# FD_Capacitance_Sensor_v13B.net
KiCad netlist of a schematic drawn in EAGLE
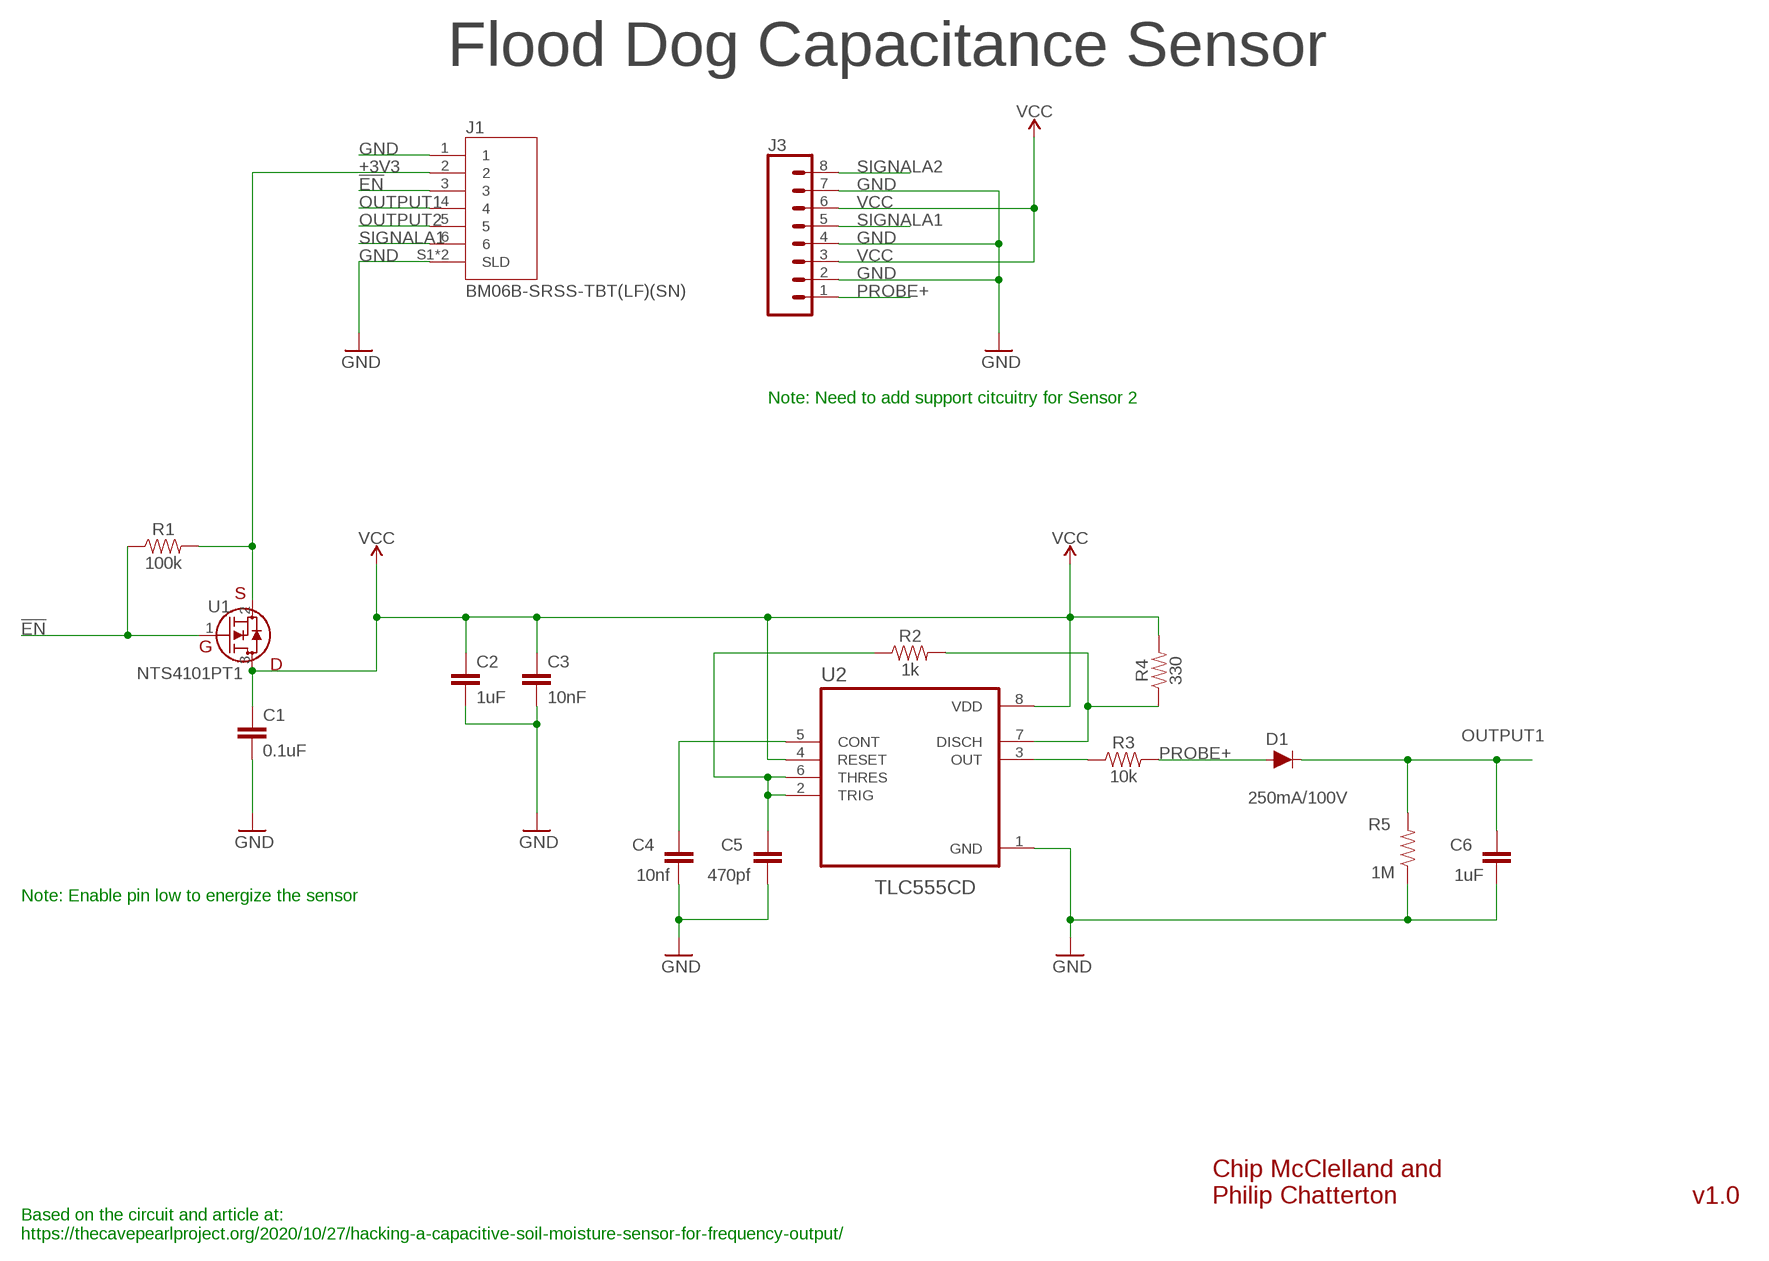
[diagram p0: schematic, sheet 1]

(export (version "E")
  (design (tool "Eeschema 10.0.6"))
  (components
    (comp (ref "C1")
      (value "0.1uF")
      (footprint "eagle-import:0805@1")
      (fields (field (name "HOUSEPART") "YES") (field (name "MPN") "MF-CAP-0805-0.1uF"))
      (libsource (lib "eagle-import") (part "CAP-MF-0.1UF-0805"))
    )
    (comp (ref "C2")
      (value "1uF")
      (footprint "eagle-import:0805@1")
      (fields (field (name "HOUSEPART") "yes") (field (name "MPN") "MF-CAP-0805-1uF"))
      (libsource (lib "eagle-import") (part "CAP-MF-1UF-0805"))
    )
    (comp (ref "C3")
      (value "10nF")
      (footprint "eagle-import:0805@1")
      (fields (field (name "HOUSEPART") "NO") (field (name "MPN") "C0805X103K1RAC3316"))
      (libsource (lib "eagle-import") (part "CAP-10NF-0805"))
    )
    (comp (ref "C4")
      (value "10nf")
      (footprint "eagle-import:C0805")
      (libsource (lib "eagle-import") (part "C-EUC0805"))
    )
    (comp (ref "C5")
      (value "470pf")
      (footprint "eagle-import:C0805")
      (libsource (lib "eagle-import") (part "C-EUC0805"))
    )
    (comp (ref "C6")
      (value "1uF")
      (footprint "eagle-import:C0805")
      (libsource (lib "eagle-import") (part "C-EUC0805"))
    )
    (comp (ref "D1")
      (value "250mA/100V")
      (footprint "eagle-import:SOD-323")
      (fields (field (name "MPN") "BAS16HT1G"))
      (libsource (lib "eagle-import") (part "DIODE-BAS16J"))
    )
    (comp (ref "J1")
      (value "BM06B-SRSS-TBT(LF)(SN)")
      (footprint "eagle-import:JST_BM06B-SRSS-TB(LF)(SN)")
      (libsource (lib "eagle-import") (part "BM06B-SRSS-TBT(LF)(SN)"))
    )
    (comp (ref "J3")
      (value "CONN_08\"")
      (footprint "eagle-import:1X08")
      (libsource (lib "eagle-import") (part "CONN_08{dblquote}"))
    )
    (comp (ref "R1")
      (value "100k")
      (footprint "eagle-import:0805")
      (fields (field (name "MPN") "MF-RES-0805-100K") (field (name "MPN_1") "MF-RES-0805-100K"))
      (libsource (lib "eagle-import") (part "RESISTOR-MF-100K-0805"))
    )
    (comp (ref "R2")
      (value "1k")
      (footprint "eagle-import:0805")
      (fields (field (name "HOUSEPART") "YES") (field (name "MPN") "MF-RES-0805-1K"))
      (libsource (lib "eagle-import") (part "RESISTOR-MF-1K-0805"))
    )
    (comp (ref "R3")
      (value "10k")
      (footprint "eagle-import:0805")
      (fields (field (name "MPN") "MF-RES-0805-10K"))
      (libsource (lib "eagle-import") (part "RESISTOR-MF-10K-0805"))
    )
    (comp (ref "R4")
      (value "330")
      (footprint "eagle-import:0805")
      (fields (field (name "HOUSEPART") "YES") (field (name "MPN") "MF-RES-0805-330"))
      (libsource (lib "eagle-import") (part "RESISTOR-MF-330-0805"))
    )
    (comp (ref "R5")
      (value "1M")
      (footprint "eagle-import:0805")
      (fields (field (name "HOUSEPART") "YES") (field (name "MPN") "MF-RES-0805-1K"))
      (libsource (lib "eagle-import") (part "RESISTOR-MF-1K-0805"))
    )
    (comp (ref "U1")
      (value "NTS4101PT1")
      (footprint "eagle-import:SOT_101PT1_ONS")
      (libsource (lib "eagle-import") (part "NTS4101PT1"))
    )
    (comp (ref "U2")
      (value "TLC555CD")
      (footprint "eagle-import:SOIC127P599X175-8N")
      (fields (field (name "DIGI-KEY_PART_NUMBER") "296-52992-ND") (field (name "MF") "Texas Instruments"))
      (libsource (lib "eagle-import") (part "TLC555CD"))
    )
  )
  (nets
    (net (code "1") (name "/+3V3") (class "Default")
      (node (ref "J1") (pin "2") (pinfunction "2_2") (pintype "passive"))
      (node (ref "R1") (pin "2") (pinfunction "2_2") (pintype "passive"))
      (node (ref "U1") (pin "2") (pinfunction "S_2") (pintype "passive"))
    )
    (net (code "2") (name "/OUTPUT1") (class "Default")
      (node (ref "C6") (pin "2") (pinfunction "2_2") (pintype "passive"))
      (node (ref "D1") (pin "C") (pinfunction "C_C") (pintype "passive"))
      (node (ref "J1") (pin "4") (pinfunction "4_4") (pintype "passive"))
      (node (ref "R5") (pin "2") (pinfunction "2_2") (pintype "passive"))
    )
    (net (code "3") (name "/OUTPUT2") (class "Default")
      (node (ref "J1") (pin "5") (pinfunction "5_5") (pintype "passive"))
    )
    (net (code "4") (name "/PROBE+") (class "Default")
      (node (ref "D1") (pin "A") (pinfunction "A_A") (pintype "passive"))
      (node (ref "J3") (pin "1") (pinfunction "1_1") (pintype "passive"))
      (node (ref "R3") (pin "2") (pinfunction "2_2") (pintype "passive"))
    )
    (net (code "5") (name "/SIGNALA1") (class "Default")
      (node (ref "J1") (pin "6") (pinfunction "6_6") (pintype "passive"))
      (node (ref "J3") (pin "5") (pinfunction "5_5") (pintype "passive"))
    )
    (net (code "6") (name "/SIGNALA2") (class "Default")
      (node (ref "J3") (pin "8") (pinfunction "8_8") (pintype "passive"))
    )
    (net (code "7") (name "/~{EN}") (class "Default")
      (node (ref "J1") (pin "3") (pinfunction "3_3") (pintype "passive"))
      (node (ref "R1") (pin "1") (pinfunction "1_1") (pintype "passive"))
      (node (ref "U1") (pin "1") (pinfunction "G_1") (pintype "passive"))
    )
    (net (code "8") (name "GND") (class "Default")
      (node (ref "C1") (pin "2") (pinfunction "2_2") (pintype "passive"))
      (node (ref "C2") (pin "2") (pinfunction "2_2") (pintype "passive"))
      (node (ref "C3") (pin "2") (pinfunction "2_2") (pintype "passive"))
      (node (ref "C4") (pin "1") (pinfunction "1_1") (pintype "passive"))
      (node (ref "C5") (pin "1") (pinfunction "1_1") (pintype "passive"))
      (node (ref "C6") (pin "1") (pinfunction "1_1") (pintype "passive"))
      (node (ref "J1") (pin "1") (pinfunction "1_1") (pintype "passive"))
      (node (ref "J1") (pin "S1") (pinfunction "SLD_S1") (pintype "passive"))
      (node (ref "J1") (pin "S2") (pinfunction "SLD_S2") (pintype "passive"))
      (node (ref "J3") (pin "2") (pinfunction "2_2") (pintype "passive"))
      (node (ref "J3") (pin "4") (pinfunction "4_4") (pintype "passive"))
      (node (ref "J3") (pin "7") (pinfunction "7_7") (pintype "passive"))
      (node (ref "R5") (pin "1") (pinfunction "1_1") (pintype "passive"))
      (node (ref "U2") (pin "1") (pinfunction "GND_1") (pintype "power_in"))
    )
    (net (code "9") (name "Net-(U2-CONT)") (class "Default")
      (node (ref "C4") (pin "2") (pinfunction "2_2") (pintype "passive"))
      (node (ref "U2") (pin "5") (pinfunction "CONT_5") (pintype "input"))
    )
    (net (code "10") (name "Net-(U2-DISCH)") (class "Default")
      (node (ref "R2") (pin "2") (pinfunction "2_2") (pintype "passive"))
      (node (ref "R4") (pin "1") (pinfunction "1_1") (pintype "passive"))
      (node (ref "U2") (pin "7") (pinfunction "DISCH_7") (pintype "output"))
    )
    (net (code "11") (name "Net-(U2-OUT)") (class "Default")
      (node (ref "R3") (pin "1") (pinfunction "1_1") (pintype "passive"))
      (node (ref "U2") (pin "3") (pinfunction "OUT_3") (pintype "output"))
    )
    (net (code "12") (name "Net-(U2-THRES)") (class "Default")
      (node (ref "C5") (pin "2") (pinfunction "2_2") (pintype "passive"))
      (node (ref "R2") (pin "1") (pinfunction "1_1") (pintype "passive"))
      (node (ref "U2") (pin "2") (pinfunction "TRIG_2") (pintype "input"))
      (node (ref "U2") (pin "6") (pinfunction "THRES_6") (pintype "input"))
    )
    (net (code "13") (name "VCC") (class "Default")
      (node (ref "C1") (pin "1") (pinfunction "1_1") (pintype "passive"))
      (node (ref "C2") (pin "1") (pinfunction "1_1") (pintype "passive"))
      (node (ref "C3") (pin "1") (pinfunction "1_1") (pintype "passive"))
      (node (ref "J3") (pin "3") (pinfunction "3_3") (pintype "passive"))
      (node (ref "J3") (pin "6") (pinfunction "6_6") (pintype "passive"))
      (node (ref "R4") (pin "2") (pinfunction "2_2") (pintype "passive"))
      (node (ref "U1") (pin "3") (pinfunction "D_3") (pintype "passive"))
      (node (ref "U2") (pin "4") (pinfunction "RESET_4") (pintype "input"))
      (node (ref "U2") (pin "8") (pinfunction "VDD_8") (pintype "power_in"))
    )
  )
)
